# PROC091F_ANALOG_MUX.net
KiCad netlist of a schematic drawn in Altium Designer
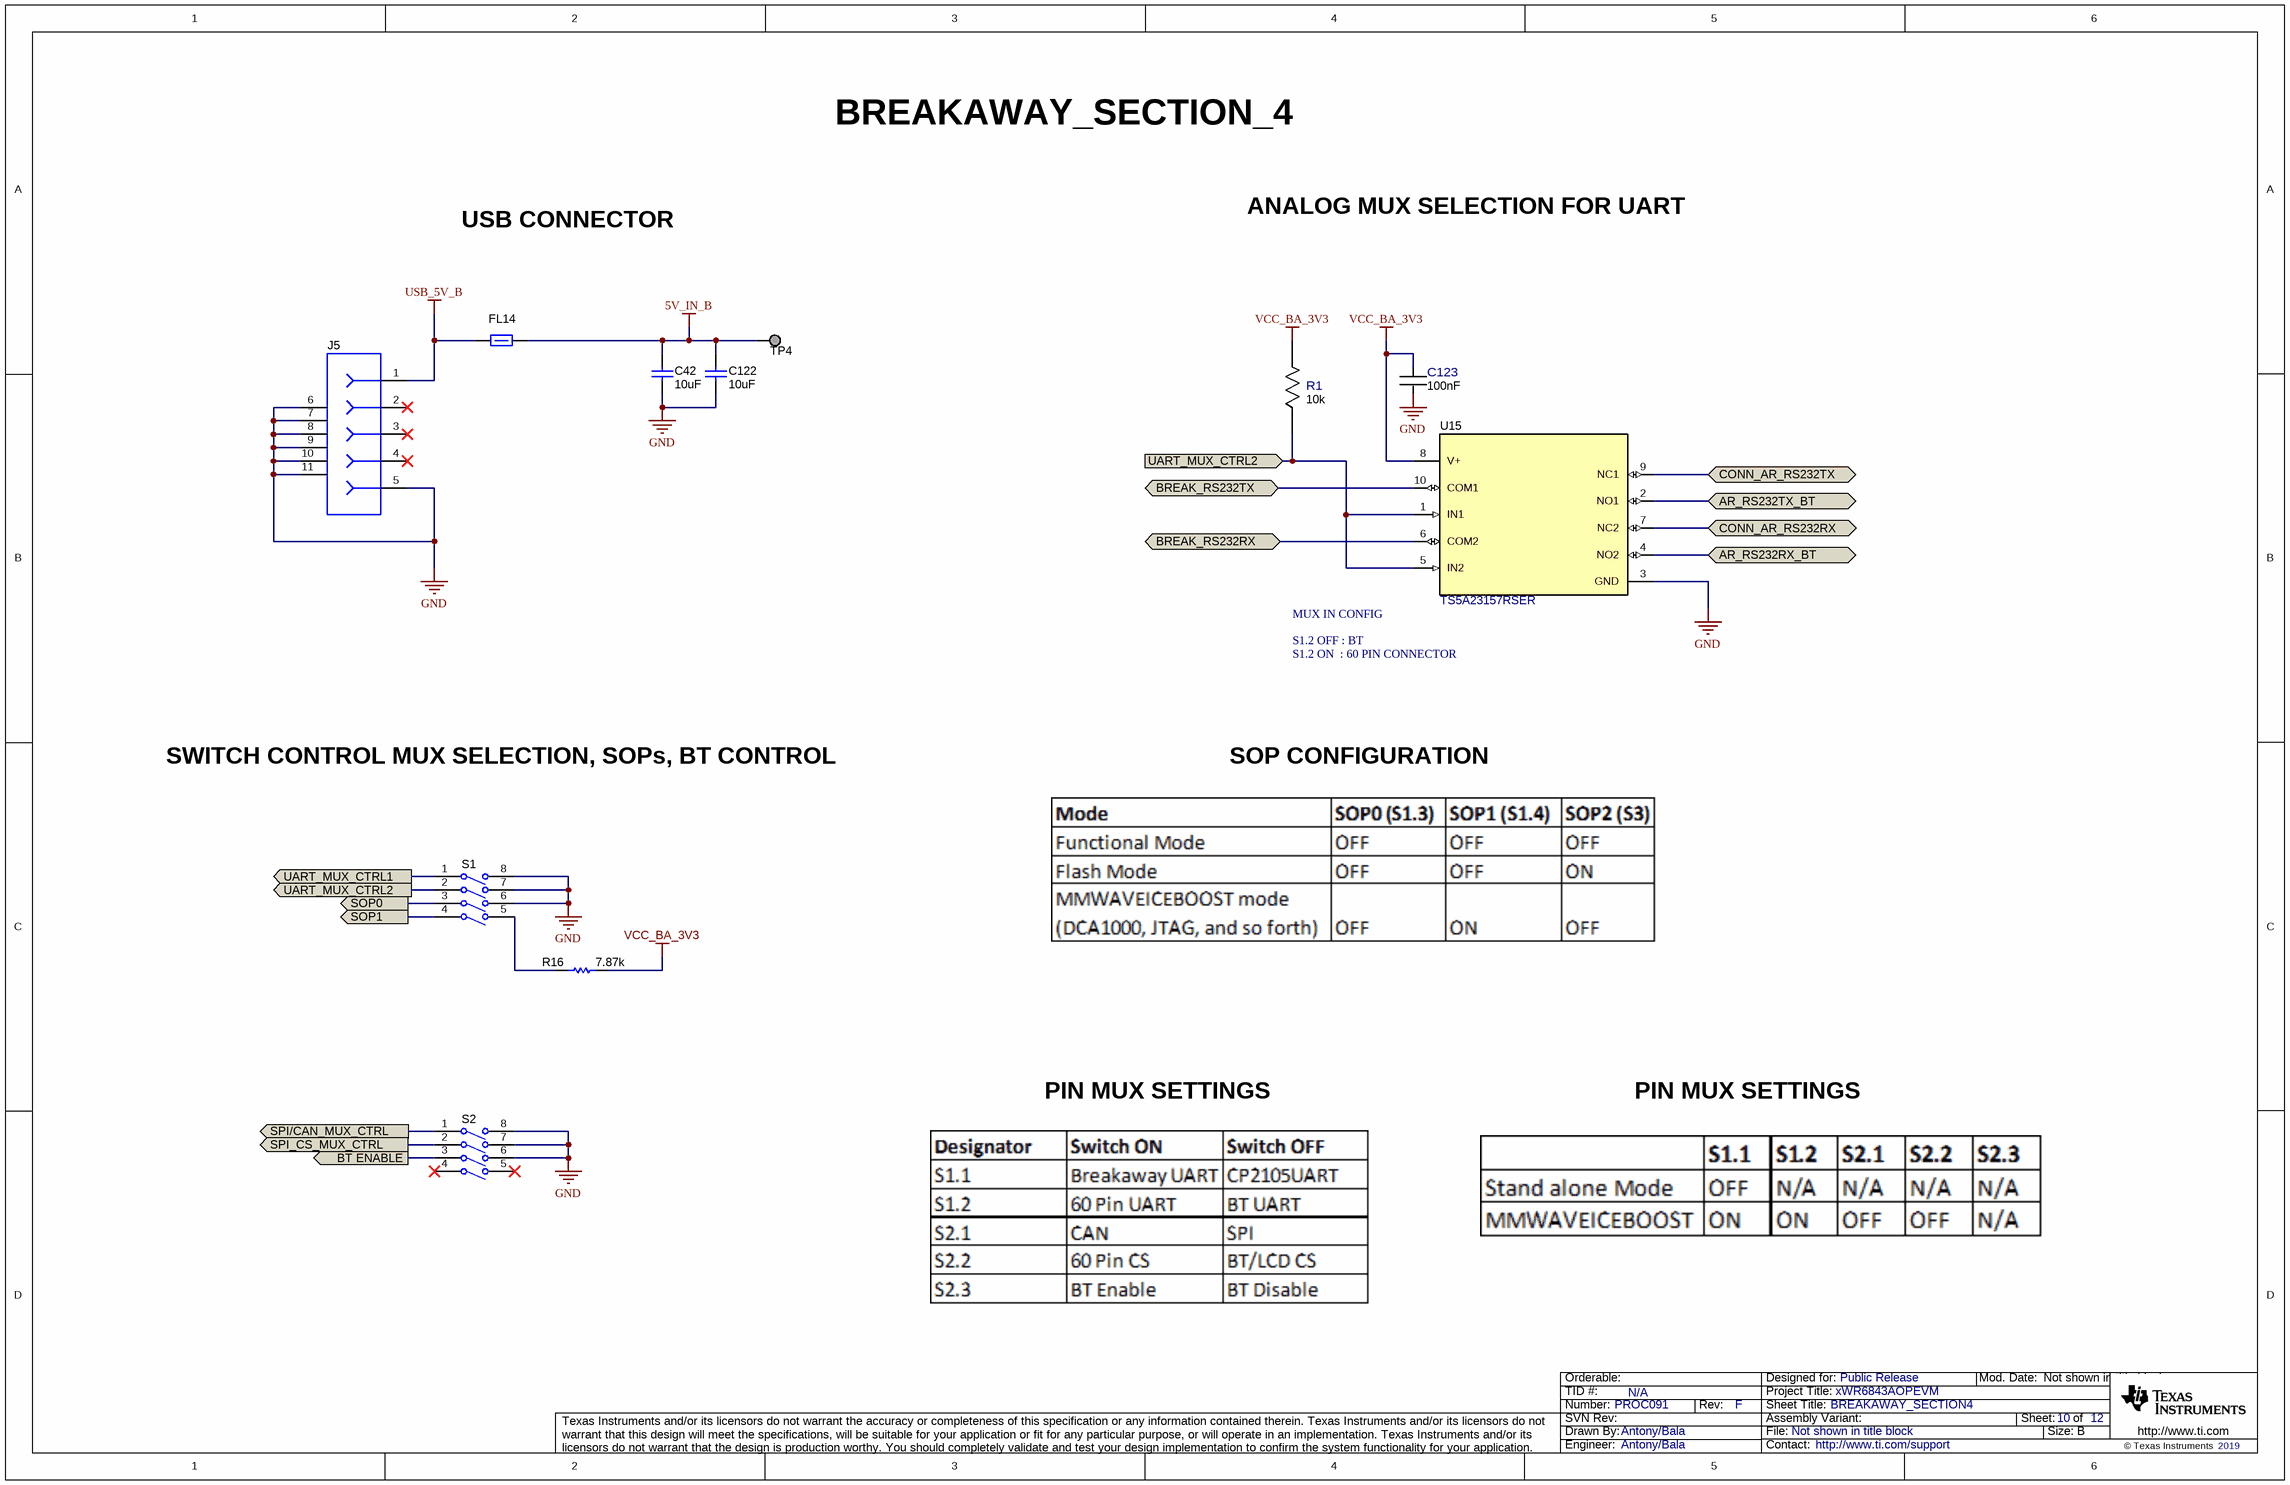
[diagram p0: PROC091F_ANALOG_MUX.SchDoc]

(export (version "E")
  (design (tool "Eeschema 10.0.6"))
  (components
    (comp (ref "C42")
      (value "10uF")
      (footprint "0402_070")
      (description "CAP, CERM, 10 uF, 10 V, +/- 20%, X5R, 0402")
      (fields
        (field (name "MANUFACTURER") "Samsung Electro-Mechanics")
        (field (name "PARTNUMBER") "CL05A106MP5NUNC")
      )
      (libsource (lib "Altium Vault - TI") (part "Capacitor"))
    )
    (comp (ref "C122")
      (value "10uF")
      (footprint "0402_070")
      (description "CAP, CERM, 10 uF, 10 V, +/- 20%, X5R, 0402")
      (fields
        (field (name "MANUFACTURER") "Samsung Electro-Mechanics")
        (field (name "PARTNUMBER") "CL05A106MP5NUNC")
      )
      (libsource (lib "Altium Vault - TI") (part "Capacitor"))
    )
    (comp (ref "C123")
      (value "GRM033R6YA104KE14D")
      (footprint "FP-GRM033R6YA104KE14D_0201 (0603 Metric)-IPC_C")
      (description "Cap Ceramic 0.1uF 35V X5R 10% Pad SMD 0201 85C T/R")
      (fields (field (name "CAP_F") "100nF") (field (name "MANUFACTURER") "Murata Electronics North America"))
      (libsource (lib "Altium Vault - TI") (part "SYM-B32642B0223J"))
    )
    (comp (ref "FL14")
      (value "BLM15PD300SZ1D")
      (footprint "0402L")
      (description "Inductor, Ferrite Bead, Ferrite, 2.2 A, 0.035 ohm, AEC-Q200 Grade 1, SMD")
      (fields (field (name "MANUFACTURER") "MuRata") (field (name "PUBLISHER") "Texas Instruments"))
      (libsource (lib "Altium Vault - TI") (part "Ferrite_Bead"))
    )
    (comp (ref "J5")
      (value "105017-0001")
      (footprint "CONN_105017-0001")
      (description "Connector, Receptacle, Micro-USB Type B, R/A, Bottom Mount SMT")
      (fields (field (name "MANUFACTURER") "Molex") (field (name "PUBLISHER") "Texas Instruments"))
      (libsource (lib "Altium Vault - TI") (part "CONN_105017-0001"))
    )
    (comp (ref "R1")
      (value "RR0306P-103-D")
      (footprint "FP-RR0306P-103-D_0201-IPC_C")
      (description "10 kOhms ±0.5% 0.05W, 1/20W Chip Resistor 0201 (0603 Metric)  Thin Film")
      (fields (field (name "MANUFACTURER") "Susumu") (field (name "RES_OHM") "10k"))
      (libsource (lib "Altium Vault - TI") (part "SYM-PMR18EZPJ000"))
    )
    (comp (ref "R16")
      (value "7.87k")
      (footprint "0201L")
      (description "RES, 7.87 k, 1%, 0.05 W, 0201")
      (fields
        (field (name "MANUFACTURER") "Yageo America")
        (field (name "PARTNUMBER") "RC0201FR-077K87L")
        (field (name "PUBLISHER") "Texas Instruments")
      )
      (libsource (lib "Altium Vault - TI") (part "Resistor"))
    )
    (comp (ref "S1")
      (value "218-4LPST")
      (footprint "SW_218-4LPST")
      (description "Switch, Slide, SPST 4 poles, SMT")
      (fields
        (field (name "MANUFACTURER") "CTS Electrocomponents")
        (field (name "PUBLISHER") "Texas Instruments")
      )
      (libsource (lib "Altium Vault - TI") (part "SW_4SPST"))
    )
    (comp (ref "S2")
      (value "218-4LPST")
      (footprint "SW_218-4LPST")
      (description "Switch, Slide, SPST 4 poles, SMT")
      (fields
        (field (name "MANUFACTURER") "CTS Electrocomponents")
        (field (name "PUBLISHER") "Texas Instruments")
      )
      (libsource (lib "Altium Vault - TI") (part "SW_4SPST"))
    )
    (comp (ref "TP4")
      (value "TESTPOINT")
      (footprint "TP_25MIL-SMT")
      (description "TEST POINT.  No entry in BOM.")
      (libsource (lib "Altium Vault - TI") (part "TESTPOINT"))
    )
    (comp (ref "U15")
      (value "TS5A23157RSER")
      (footprint "RSE0010A")
      (description "Dual 10-ohm SPDT Analog Switch, RSE0010A (UQFN-10)")
      (fields
        (field (name "MANUFACTURER") "Texas Instruments")
        (field (name "PUBLISHER") "Texas Instruments")
      )
      (libsource (lib "Altium Vault - TI") (part "TS5A23159"))
    )
  )
  (nets
    (net (code "1") (name "/AR_RS232RX_BT") (class "Default")
      (node (ref "U15") (pin "4") (pinfunction "NO2_4") (pintype "bidirectional"))
    )
    (net (code "2") (name "/AR_RS232TX_BT") (class "Default")
      (node (ref "U15") (pin "2") (pinfunction "NO1_2") (pintype "bidirectional"))
    )
    (net (code "3") (name "/BREAK_RS232RX") (class "Default")
      (node (ref "U15") (pin "6") (pinfunction "COM2_6") (pintype "bidirectional"))
    )
    (net (code "4") (name "/BREAK_RS232TX") (class "Default")
      (node (ref "U15") (pin "10") (pinfunction "COM1_10") (pintype "bidirectional"))
    )
    (net (code "5") (name "/BT ENABLE") (class "Default")
      (node (ref "S2") (pin "3") (pinfunction "A3_3") (pintype "passive"))
    )
    (net (code "6") (name "/CONN_AR_RS232RX") (class "Default")
      (node (ref "U15") (pin "7") (pinfunction "NC2_7") (pintype "bidirectional"))
    )
    (net (code "7") (name "/CONN_AR_RS232TX") (class "Default")
      (node (ref "U15") (pin "9") (pinfunction "NC1_9") (pintype "bidirectional"))
    )
    (net (code "8") (name "/SOP0") (class "Default")
      (node (ref "S1") (pin "3") (pinfunction "A3_3") (pintype "passive"))
    )
    (net (code "9") (name "/SOP1") (class "Default")
      (node (ref "S1") (pin "4") (pinfunction "A4_4") (pintype "passive"))
    )
    (net (code "10") (name "/SPI_CS_MUX_CTRL") (class "Default")
      (node (ref "S2") (pin "2") (pinfunction "A2_2") (pintype "passive"))
    )
    (net (code "11") (name "/SPI{slash}CAN_MUX_CTRL") (class "Default")
      (node (ref "S2") (pin "1") (pinfunction "A1_1") (pintype "passive"))
    )
    (net (code "12") (name "/UART_MUX_CTRL1") (class "Default")
      (node (ref "S1") (pin "1") (pinfunction "A1_1") (pintype "passive"))
    )
    (net (code "13") (name "/UART_MUX_CTRL2") (class "Default")
      (node (ref "R1") (pin "1") (pinfunction "1_1") (pintype "passive"))
      (node (ref "S1") (pin "2") (pinfunction "A2_2") (pintype "passive"))
      (node (ref "U15") (pin "1") (pinfunction "IN1_1") (pintype "input"))
      (node (ref "U15") (pin "5") (pinfunction "IN2_5") (pintype "input"))
    )
    (net (code "14") (name "5V_IN_B") (class "Default")
      (node (ref "C122") (pin "1") (pinfunction "1_1") (pintype "passive"))
      (node (ref "C42") (pin "2") (pinfunction "2_2") (pintype "passive"))
      (node (ref "FL14") (pin "2") (pinfunction "2_2") (pintype "passive"))
      (node (ref "TP4") (pin "1") (pintype "passive"))
    )
    (net (code "15") (name "GND") (class "Default")
      (node (ref "C122") (pin "2") (pinfunction "2_2") (pintype "passive"))
      (node (ref "C123") (pin "2") (pinfunction "2_2") (pintype "passive"))
      (node (ref "C42") (pin "1") (pinfunction "1_1") (pintype "passive"))
      (node (ref "J5") (pin "10") (pintype "passive"))
      (node (ref "J5") (pin "11") (pintype "passive"))
      (node (ref "J5") (pin "5") (pintype "passive"))
      (node (ref "J5") (pin "6") (pintype "passive"))
      (node (ref "J5") (pin "7") (pintype "passive"))
      (node (ref "J5") (pin "8") (pintype "passive"))
      (node (ref "J5") (pin "9") (pintype "passive"))
      (node (ref "S1") (pin "6") (pinfunction "B3_6") (pintype "passive"))
      (node (ref "S1") (pin "7") (pinfunction "B2_7") (pintype "passive"))
      (node (ref "S1") (pin "8") (pinfunction "B1_8") (pintype "passive"))
      (node (ref "S2") (pin "6") (pinfunction "B3_6") (pintype "passive"))
      (node (ref "S2") (pin "7") (pinfunction "B2_7") (pintype "passive"))
      (node (ref "S2") (pin "8") (pinfunction "B1_8") (pintype "passive"))
      (node (ref "U15") (pin "3") (pinfunction "GND_3") (pintype "power_in"))
    )
    (net (code "16") (name "Net-(S1-B4)") (class "Default")
      (node (ref "R16") (pin "2") (pinfunction "2_2") (pintype "passive"))
      (node (ref "S1") (pin "5") (pinfunction "B4_5") (pintype "passive"))
    )
    (net (code "17") (name "USB_5V_B") (class "Default")
      (node (ref "FL14") (pin "1") (pinfunction "1_1") (pintype "passive"))
      (node (ref "J5") (pin "1") (pintype "passive"))
    )
    (net (code "18") (name "VCC_BA_3V3") (class "Default")
      (node (ref "C123") (pin "1") (pinfunction "1_1") (pintype "passive"))
      (node (ref "R1") (pin "2") (pinfunction "2_2") (pintype "passive"))
      (node (ref "R16") (pin "1") (pinfunction "1_1") (pintype "passive"))
      (node (ref "U15") (pin "8") (pinfunction "V+_8") (pintype "power_in"))
    )
    (net (code "19") (name "unconnected-(J5-Pad2)") (class "Default")
      (node (ref "J5") (pin "2") (pintype "passive+no_connect"))
    )
    (net (code "20") (name "unconnected-(J5-Pad3)") (class "Default")
      (node (ref "J5") (pin "3") (pintype "passive+no_connect"))
    )
    (net (code "21") (name "unconnected-(J5-Pad4)") (class "Default")
      (node (ref "J5") (pin "4") (pintype "passive+no_connect"))
    )
    (net (code "22") (name "unconnected-(S2-A4-Pad4)") (class "Default")
      (node (ref "S2") (pin "4") (pinfunction "A4_4") (pintype "passive+no_connect"))
    )
    (net (code "23") (name "unconnected-(S2-B4-Pad5)") (class "Default")
      (node (ref "S2") (pin "5") (pinfunction "B4_5") (pintype "passive+no_connect"))
    )
  )
)
